# Battery_Management_and_Charging.net
KiCad netlist of a schematic drawn in Altium Designer
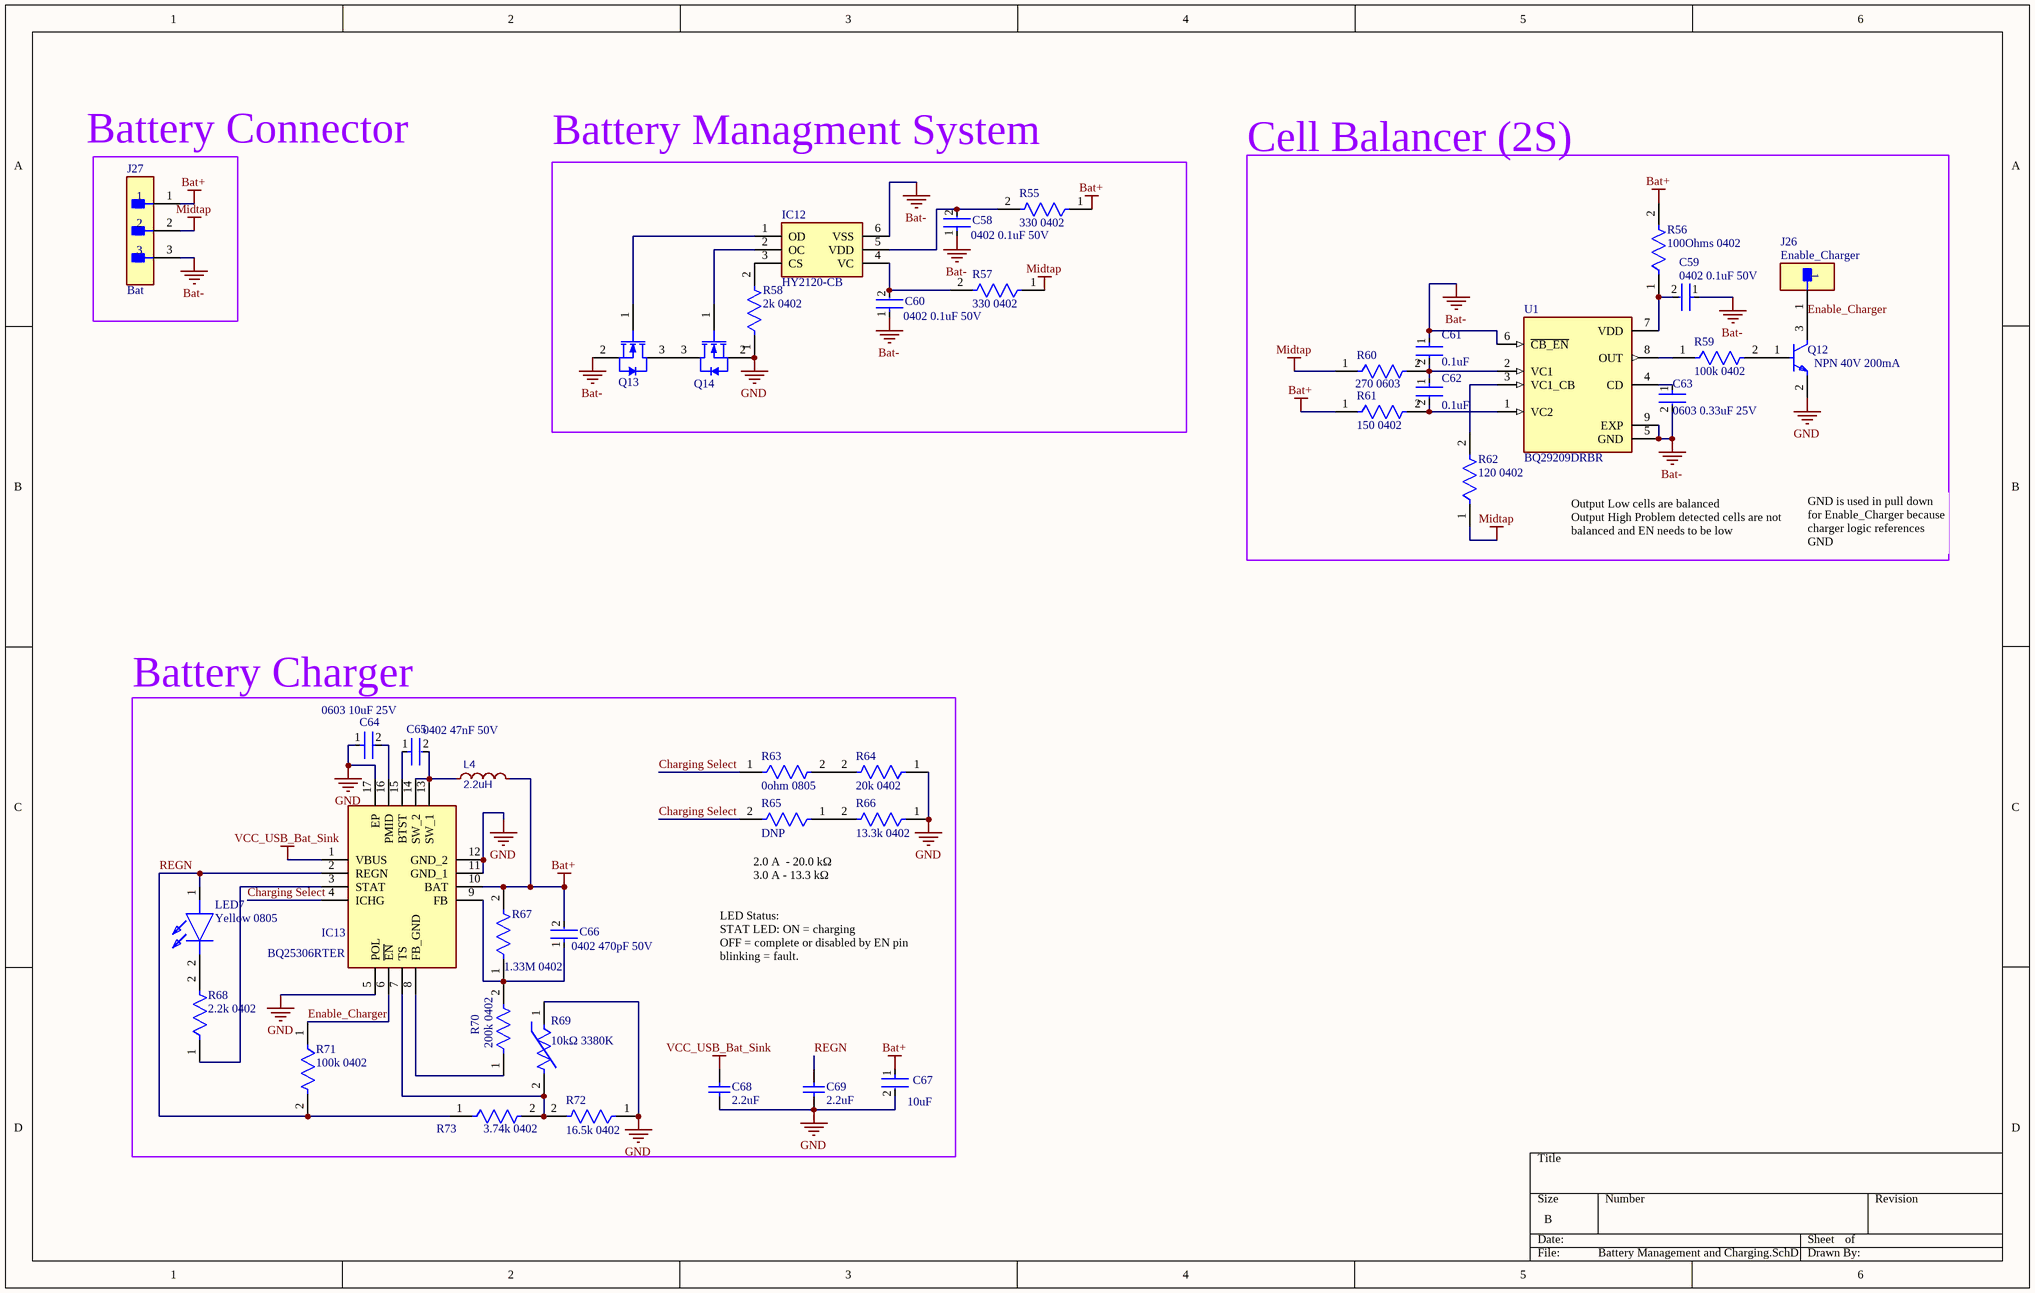
[diagram p0: Battery Management and Charging.SchDoc]

(export (version "E")
  (design (tool "Eeschema 10.0.6"))
  (components
    (comp (ref "C58")
      (value "0402 0.1uF 50V")
      (footprint "FP-C0402-BB-MFG")
      (description "C307331")
      (fields
        (field (name "TOLERANCE") "0.2")
        (field (name "OCTOPART") "https://octopart.com/c0402c104m3pac7867-kemet-84304880")
      )
      (libsource (lib "Altium Content Vault") (part "b4654b650e69147ec39a6b967a45e02"))
    )
    (comp (ref "C59")
      (value "0402 0.1uF 50V")
      (footprint "FP-C0402-BB-MFG")
      (description "C307331")
      (fields
        (field (name "TOLERANCE") "0.2")
        (field (name "OCTOPART") "https://octopart.com/c0402c104m3pac7867-kemet-84304880")
      )
      (libsource (lib "Altium Content Vault") (part "b4654b650e69147ec39a6b967a45e02"))
    )
    (comp (ref "C60")
      (value "0402 0.1uF 50V")
      (footprint "FP-C0402-BB-MFG")
      (description "C307331")
      (fields
        (field (name "TOLERANCE") "0.2")
        (field (name "OCTOPART") "https://octopart.com/c0402c104m3pac7867-kemet-84304880")
      )
      (libsource (lib "Altium Content Vault") (part "b4654b650e69147ec39a6b967a45e02"))
    )
    (comp (ref "C61")
      (value "0.1uF")
      (footprint "FP-C0402-BB-MFG")
      (description "C307331")
      (fields
        (field (name "TOLERANCE") "0.2")
        (field (name "OCTOPART") "https://octopart.com/c0402c104m3pac7867-kemet-84304880")
      )
      (libsource (lib "Altium Content Vault") (part "b4654b650e69147ec39a6b967a45e02"))
    )
    (comp (ref "C62")
      (value "0.1uF")
      (footprint "FP-C0402-BB-MFG")
      (description "C307331")
      (fields
        (field (name "TOLERANCE") "0.2")
        (field (name "OCTOPART") "https://octopart.com/c0402c104m3pac7867-kemet-84304880")
      )
      (libsource (lib "Altium Content Vault") (part "b4654b650e69147ec39a6b967a45e02"))
    )
    (comp (ref "C63")
      (value "0603 0.33uF 25V")
      (footprint "FP-CC0603-DC-MFG")
      (description "C1615")
      (fields (field (name "TOLERANCE") "10%"))
      (libsource (lib "Altium Content Vault") (part "b4654b650e69147ec39a6b967a45e02"))
    )
    (comp (ref "C64")
      (value "0603 10uF 25V")
      (footprint "FP-CC0603-DC-MFG")
      (description "C96446")
      (fields (field (name "TOLERANCE") "10%"))
      (libsource (lib "Altium Content Vault") (part "b4654b650e69147ec39a6b967a45e02"))
    )
    (comp (ref "C65")
      (value "0402 47nF 50V")
      (footprint "FP-C0402-BB-MFG")
      (description "C7393874")
      (fields
        (field (name "TOLERANCE") "0.2")
        (field (name "OCTOPART") "https://octopart.com/c0402c104m3pac7867-kemet-84304880")
      )
      (libsource (lib "Altium Content Vault") (part "b4654b650e69147ec39a6b967a45e02"))
    )
    (comp (ref "C66")
      (value "0402 470pF 50V")
      (footprint "FP-C0402-BB-MFG")
      (description "C1537")
      (fields
        (field (name "TOLERANCE") "0.2")
        (field (name "OCTOPART") "https://octopart.com/c0402c104m3pac7867-kemet-84304880")
      )
      (libsource (lib "Altium Content Vault") (part "b4654b650e69147ec39a6b967a45e02"))
    )
    (comp (ref "C67")
      (value "10uF")
      (footprint "FP-CC0603-DC-MFG")
      (description "C96446")
      (fields (field (name "TOLERANCE") "10%"))
      (libsource (lib "Altium Content Vault") (part "b4654b650e69147ec39a6b967a45e02"))
    )
    (comp (ref "C68")
      (value "2.2uF")
      (footprint "CAPC2013X94X50LL20T25")
      (description "C377773")
      (fields
        (field (name "PART NUMBER") "08051C102KAT4A")
        (field (name "MANUFACTURER") "AVX Interconnect / Elco")
      )
      (libsource (lib "Altium Content Vault") (part "CAP"))
    )
    (comp (ref "C69")
      (value "2.2uF")
      (footprint "CAPC2013X94X50LL20T25")
      (description "C377773")
      (fields
        (field (name "PART NUMBER") "08051C102KAT4A")
        (field (name "MANUFACTURER") "AVX Interconnect / Elco")
      )
      (libsource (lib "Altium Content Vault") (part "CAP"))
    )
    (comp (ref "IC12")
      (value "HY2120-CB")
      (footprint "PcbLib1:SOT95P280X140-6N")
      (description "C116509")
      (libsource (lib "*") (part "HY2120-CB"))
    )
    (comp (ref "IC13")
      (value "BQ25306RTER")
      (footprint "PcbLib1:QFN50P300X300X80-17N-D")
      (description "C3682611")
      (fields (field (name "MOUSER PART NUMBER") "595-BQ25306RTER"))
      (libsource (lib "*") (part "BQ25306RTER"))
    )
    (comp (ref "J26")
      (value "Enable_Charger")
      (footprint "FP-5015-MFG")
      (description "PC TEST POINT MINIATURE")
      (fields (field (name "MANUFACTURER PART NUMBER") "5015") (field (name "MANUFACTURER") "keystone"))
      (libsource (lib "Altium Content Vault") (part "dd45045ce8184df9e99e12baf3f412c"))
    )
    (comp (ref "J27")
      (value "Bat")
      (footprint "FP-TSW-103-14-G-S-MFG")
      (description "CONN HEADER VERT 3POS 2.54MM")
      (libsource (lib "Altium Content Vault") (part "cd3439d6ef35ae5d9b27ec4fdd3e828"))
    )
    (comp (ref "L4")
      (value "2.2uH")
      (footprint "2.2uH")
      (description "C177247")
      (fields
        (field (name "MANUFACTURER") "cjiang(长江微电)")
        (field (name "MANUFACTURER PART") "FXL0530-2R2-M")
        (field (name "CONTRIBUTOR") "LCSC")
      )
      (libsource (lib "Schlib1") (part "2.2uH"))
    )
    (comp (ref "LED7")
      (value "Yellow 0805")
      (footprint "SamacSys:KT0805G")
      (description "C2296")
      (fields (field (name "MANUFACTURER_PART_NUMBER") "KT-0805G"))
      (libsource (lib "*") (part "KT-0805G"))
    )
    (comp (ref "Q12")
      (value "NPN 40V 200mA")
      (footprint "FP-SOT23-IPC_A")
      (description "C364310")
      (libsource (lib "Altium Content Vault") (part "b44e953556f554d0102664c7d152cb4"))
    )
    (comp (ref "Q13")
      (value "Discharge Protection")
      (footprint "ONSC-SOT-23-3-318-08_V")
      (description "C20917")
      (fields (field (name "MANUFACTURER") "On Semiconductor") (field (name "PARTNUMBER") "2N7002LT1G"))
      (libsource (lib "Altium Content Vault") (part "ONSC-NMOS-G1S2D3-3"))
    )
    (comp (ref "Q14")
      (value "Discharge Protection")
      (footprint "ONSC-SOT-23-3-318-08_V")
      (description "C20917")
      (fields (field (name "MANUFACTURER") "On Semiconductor") (field (name "PARTNUMBER") "2N7002LT1G"))
      (libsource (lib "Altium Content Vault") (part "ONSC-NMOS-G1S2D3-3"))
    )
    (comp (ref "R55")
      (value "330 0402")
      (footprint "FP-RMCF0402-MFG")
      (description "C25104")
      (fields (field (name "TOLERANCE") "5%"))
      (libsource (lib "Altium Content Vault") (part "1029c3af85768c4190bb7ad29bc67b5"))
    )
    (comp (ref "R56")
      (value "100Ohms 0402")
      (footprint "FP-RMCF0402-MFG")
      (description "C25076")
      (fields (field (name "TOLERANCE") "5%"))
      (libsource (lib "Altium Content Vault") (part "1029c3af85768c4190bb7ad29bc67b5"))
    )
    (comp (ref "R57")
      (value "330 0402")
      (footprint "FP-RMCF0402-MFG")
      (description "C25104")
      (fields (field (name "TOLERANCE") "5%"))
      (libsource (lib "Altium Content Vault") (part "1029c3af85768c4190bb7ad29bc67b5"))
    )
    (comp (ref "R58")
      (value "2k 0402")
      (footprint "FP-RMCF0402-MFG")
      (description "C4109")
      (fields (field (name "TOLERANCE") "5%"))
      (libsource (lib "Altium Content Vault") (part "1029c3af85768c4190bb7ad29bc67b5"))
    )
    (comp (ref "R59")
      (value "100k 0402")
      (footprint "FP-RMCF0402-MFG")
      (description "C25741")
      (fields (field (name "TOLERANCE") "5%"))
      (libsource (lib "Altium Content Vault") (part "1029c3af85768c4190bb7ad29bc67b5"))
    )
    (comp (ref "R60")
      (value "270 0603")
      (footprint "FP-AC0603-MFG")
      (description "C22966")
      (fields (field (name "TOLERANCE") "1%"))
      (libsource (lib "Altium Content Vault") (part "1029c3af85768c4190bb7ad29bc67b5"))
    )
    (comp (ref "R61")
      (value "150 0402")
      (footprint "FP-RMCF0402-MFG")
      (description "C25082")
      (fields (field (name "TOLERANCE") "5%"))
      (libsource (lib "Altium Content Vault") (part "1029c3af85768c4190bb7ad29bc67b5"))
    )
    (comp (ref "R62")
      (value "120 0402")
      (footprint "FP-RMCF0402-MFG")
      (description "C25079")
      (fields (field (name "TOLERANCE") "5%"))
      (libsource (lib "Altium Content Vault") (part "1029c3af85768c4190bb7ad29bc67b5"))
    )
    (comp (ref "R63")
      (value "0ohm 0805")
      (footprint "FP-RN73R2A-IPC_C")
      (description "C17477")
      (libsource (lib "Altium Content Vault") (part "1029c3af85768c4190bb7ad29bc67b5"))
    )
    (comp (ref "R64")
      (value "20k 0402")
      (footprint "FP-RMCF0402-MFG")
      (description "C25765")
      (fields (field (name "TOLERANCE") "5%"))
      (libsource (lib "Altium Content Vault") (part "1029c3af85768c4190bb7ad29bc67b5"))
    )
    (comp (ref "R65")
      (value "DNP")
      (footprint "FP-RN73R2A-IPC_C")
      (description "DNP 0805")
      (libsource (lib "Altium Content Vault") (part "1029c3af85768c4190bb7ad29bc67b5"))
    )
    (comp (ref "R66")
      (value "13.3k 0402")
      (footprint "FP-RMCF0402-MFG")
      (description "C2974007")
      (fields (field (name "TOLERANCE") "5%"))
      (libsource (lib "Altium Content Vault") (part "1029c3af85768c4190bb7ad29bc67b5"))
    )
    (comp (ref "R67")
      (value "1.33M 0402")
      (footprint "FP-RMCF0402-MFG")
      (description "C5713265")
      (fields (field (name "TOLERANCE") "5%"))
      (libsource (lib "Altium Content Vault") (part "1029c3af85768c4190bb7ad29bc67b5"))
    )
    (comp (ref "R68")
      (value "2.2k 0402")
      (footprint "FP-AF0402-IPC_B")
      (description "C25879")
      (fields (field (name "TOLERANCE") "5%"))
      (libsource (lib "Altium Content Vault") (part "1029c3af85768c4190bb7ad29bc67b5"))
    )
    (comp (ref "R69")
      (value "10kΩ 3380K")
      (footprint "FP-NCP15-NCU15-0_05-IPC_A")
      (description "C178739")
      (libsource (lib "Altium Content Vault") (part "3b148a6ebabc5fb4d708a66c052d352"))
    )
    (comp (ref "R70")
      (value "200k 0402")
      (footprint "FP-RMCF0402-MFG")
      (description "C25764")
      (fields (field (name "TOLERANCE") "5%"))
      (libsource (lib "Altium Content Vault") (part "1029c3af85768c4190bb7ad29bc67b5"))
    )
    (comp (ref "R71")
      (value "100k 0402")
      (footprint "FP-RMCF0402-MFG")
      (description "C25741")
      (fields (field (name "TOLERANCE") "5%"))
      (libsource (lib "Altium Content Vault") (part "1029c3af85768c4190bb7ad29bc67b5"))
    )
    (comp (ref "R72")
      (value "16.5k 0402")
      (footprint "FP-RMCF0402-MFG")
      (description "C226807")
      (fields (field (name "TOLERANCE") "5%"))
      (libsource (lib "Altium Content Vault") (part "1029c3af85768c4190bb7ad29bc67b5"))
    )
    (comp (ref "R73")
      (value "3.74k 0402")
      (footprint "FP-RMCF0402-MFG")
      (description "C2986585")
      (fields (field (name "TOLERANCE") "5%"))
      (libsource (lib "Altium Content Vault") (part "1029c3af85768c4190bb7ad29bc67b5"))
    )
    (comp (ref "U1")
      (value "BQ29209DRBR")
      (footprint "Cell Balancer")
      (description "C139352")
      (fields (field (name "MF") "Texas Instruments"))
      (libsource (lib "Schlib1") (part "BQ29209DRBR"))
    )
  )
  (nets
    (net (code "1") (name "/Charging Select") (class "Default")
      (node (ref "IC13") (pin "4") (pinfunction "ICHG_4") (pintype "passive"))
      (node (ref "R63") (pin "1") (pinfunction "1_1") (pintype "passive"))
      (node (ref "R65") (pin "2") (pinfunction "2_2") (pintype "passive"))
    )
    (net (code "2") (name "/Enable_Charger") (class "Default")
      (node (ref "IC13") (pin "6") (pinfunction "~{EN}_6") (pintype "passive"))
      (node (ref "J26") (pin "1") (pinfunction "1_1") (pintype "passive"))
      (node (ref "Q12") (pin "3") (pinfunction "C_3") (pintype "passive"))
      (node (ref "R71") (pin "1") (pinfunction "1_1") (pintype "passive"))
    )
    (net (code "3") (name "/REGN") (class "Default")
      (node (ref "C69") (pin "2") (pinfunction "2_2") (pintype "passive"))
      (node (ref "IC13") (pin "2") (pinfunction "REGN_2") (pintype "passive"))
      (node (ref "LED7") (pin "1") (pinfunction "A_1") (pintype "passive"))
      (node (ref "R71") (pin "2") (pinfunction "2_2") (pintype "passive"))
      (node (ref "R73") (pin "1") (pinfunction "1_1") (pintype "passive"))
    )
    (net (code "4") (name "Bat+") (class "Default")
      (node (ref "C66") (pin "2") (pinfunction "2_2") (pintype "passive"))
      (node (ref "C67") (pin "1") (pinfunction "1_1") (pintype "passive"))
      (node (ref "IC13") (pin "10") (pinfunction "BAT_10") (pintype "passive"))
      (node (ref "J27") (pin "1") (pinfunction "1_1") (pintype "passive"))
      (node (ref "L4") (pin "2") (pinfunction "2_2") (pintype "passive"))
      (node (ref "R55") (pin "1") (pinfunction "1_1") (pintype "passive"))
      (node (ref "R56") (pin "2") (pinfunction "2_2") (pintype "passive"))
      (node (ref "R61") (pin "1") (pinfunction "1_1") (pintype "passive"))
      (node (ref "R67") (pin "2") (pinfunction "2_2") (pintype "passive"))
    )
    (net (code "5") (name "Bat-") (class "Default")
      (node (ref "C58") (pin "1") (pinfunction "1_1") (pintype "passive"))
      (node (ref "C59") (pin "1") (pinfunction "1_1") (pintype "passive"))
      (node (ref "C60") (pin "1") (pinfunction "1_1") (pintype "passive"))
      (node (ref "C61") (pin "1") (pinfunction "1_1") (pintype "passive"))
      (node (ref "C63") (pin "2") (pinfunction "2_2") (pintype "passive"))
      (node (ref "IC12") (pin "6") (pinfunction "VSS_6") (pintype "passive"))
      (node (ref "J27") (pin "3") (pinfunction "3_3") (pintype "passive"))
      (node (ref "Q13") (pin "2") (pinfunction "S_2") (pintype "passive"))
      (node (ref "U1") (pin "5") (pinfunction "GND_5") (pintype "power_in"))
      (node (ref "U1") (pin "6") (pinfunction "~{CB_EN}_6") (pintype "input"))
      (node (ref "U1") (pin "9") (pinfunction "EXP_9") (pintype "power_in"))
    )
    (net (code "6") (name "GND") (class "Default")
      (node (ref "C64") (pin "1") (pinfunction "1_1") (pintype "passive"))
      (node (ref "C67") (pin "2") (pinfunction "2_2") (pintype "passive"))
      (node (ref "C68") (pin "1") (pinfunction "1_1") (pintype "passive"))
      (node (ref "C69") (pin "1") (pinfunction "1_1") (pintype "passive"))
      (node (ref "IC13") (pin "11") (pinfunction "GND_1_11") (pintype "passive"))
      (node (ref "IC13") (pin "12") (pinfunction "GND_2_12") (pintype "passive"))
      (node (ref "IC13") (pin "17") (pinfunction "EP_17") (pintype "passive"))
      (node (ref "IC13") (pin "5") (pinfunction "POL_5") (pintype "passive"))
      (node (ref "Q12") (pin "2") (pinfunction "E_2") (pintype "passive"))
      (node (ref "Q14") (pin "2") (pinfunction "S_2") (pintype "passive"))
      (node (ref "R58") (pin "1") (pinfunction "1_1") (pintype "passive"))
      (node (ref "R64") (pin "1") (pinfunction "1_1") (pintype "passive"))
      (node (ref "R66") (pin "1") (pinfunction "1_1") (pintype "passive"))
      (node (ref "R69") (pin "1") (pinfunction "1_1") (pintype "passive"))
      (node (ref "R72") (pin "1") (pinfunction "1_1") (pintype "passive"))
    )
    (net (code "7") (name "Midtap") (class "Default")
      (node (ref "J27") (pin "2") (pinfunction "2_2") (pintype "passive"))
      (node (ref "R57") (pin "1") (pinfunction "1_1") (pintype "passive"))
      (node (ref "R60") (pin "1") (pinfunction "1_1") (pintype "passive"))
      (node (ref "R62") (pin "1") (pinfunction "1_1") (pintype "passive"))
    )
    (net (code "8") (name "Net-(IC12-CS)") (class "Default")
      (node (ref "IC12") (pin "3") (pinfunction "CS_3") (pintype "passive"))
      (node (ref "R58") (pin "2") (pinfunction "2_2") (pintype "passive"))
    )
    (net (code "9") (name "Net-(IC12-OC)") (class "Default")
      (node (ref "IC12") (pin "2") (pinfunction "OC_2") (pintype "passive"))
      (node (ref "Q14") (pin "1") (pinfunction "G_1") (pintype "passive"))
    )
    (net (code "10") (name "Net-(IC12-OD)") (class "Default")
      (node (ref "IC12") (pin "1") (pinfunction "OD_1") (pintype "passive"))
      (node (ref "Q13") (pin "1") (pinfunction "G_1") (pintype "passive"))
    )
    (net (code "11") (name "Net-(IC12-VC)") (class "Default")
      (node (ref "C60") (pin "2") (pinfunction "2_2") (pintype "passive"))
      (node (ref "IC12") (pin "4") (pinfunction "VC_4") (pintype "passive"))
      (node (ref "R57") (pin "2") (pinfunction "2_2") (pintype "passive"))
    )
    (net (code "12") (name "Net-(IC12-VDD)") (class "Default")
      (node (ref "C58") (pin "2") (pinfunction "2_2") (pintype "passive"))
      (node (ref "IC12") (pin "5") (pinfunction "VDD_5") (pintype "passive"))
      (node (ref "R55") (pin "2") (pinfunction "2_2") (pintype "passive"))
    )
    (net (code "13") (name "Net-(IC13-BTST)") (class "Default")
      (node (ref "C65") (pin "1") (pinfunction "1_1") (pintype "passive"))
      (node (ref "IC13") (pin "15") (pinfunction "BTST_15") (pintype "passive"))
    )
    (net (code "14") (name "Net-(IC13-FB)") (class "Default")
      (node (ref "C66") (pin "1") (pinfunction "1_1") (pintype "passive"))
      (node (ref "IC13") (pin "9") (pinfunction "FB_9") (pintype "passive"))
      (node (ref "R67") (pin "1") (pinfunction "1_1") (pintype "passive"))
      (node (ref "R70") (pin "2") (pinfunction "2_2") (pintype "passive"))
    )
    (net (code "15") (name "Net-(IC13-FB_GND)") (class "Default")
      (node (ref "IC13") (pin "8") (pinfunction "FB_GND_8") (pintype "passive"))
      (node (ref "R70") (pin "1") (pinfunction "1_1") (pintype "passive"))
    )
    (net (code "16") (name "Net-(IC13-PMID)") (class "Default")
      (node (ref "C64") (pin "2") (pinfunction "2_2") (pintype "passive"))
      (node (ref "IC13") (pin "16") (pinfunction "PMID_16") (pintype "passive"))
    )
    (net (code "17") (name "Net-(IC13-STAT)") (class "Default")
      (node (ref "IC13") (pin "3") (pinfunction "STAT_3") (pintype "passive"))
      (node (ref "R68") (pin "1") (pinfunction "1_1") (pintype "passive"))
    )
    (net (code "18") (name "Net-(IC13-SW_1)") (class "Default")
      (node (ref "C65") (pin "2") (pinfunction "2_2") (pintype "passive"))
      (node (ref "IC13") (pin "13") (pinfunction "SW_1_13") (pintype "passive"))
      (node (ref "IC13") (pin "14") (pinfunction "SW_2_14") (pintype "passive"))
      (node (ref "L4") (pin "1") (pinfunction "1_1") (pintype "passive"))
    )
    (net (code "19") (name "Net-(IC13-TS)") (class "Default")
      (node (ref "IC13") (pin "7") (pinfunction "TS_7") (pintype "passive"))
      (node (ref "R69") (pin "2") (pinfunction "2_2") (pintype "passive"))
      (node (ref "R72") (pin "2") (pinfunction "2_2") (pintype "passive"))
      (node (ref "R73") (pin "2") (pinfunction "2_2") (pintype "passive"))
    )
    (net (code "20") (name "Net-(LED7-K)") (class "Default")
      (node (ref "LED7") (pin "2") (pinfunction "K_2") (pintype "passive"))
      (node (ref "R68") (pin "2") (pinfunction "2_2") (pintype "passive"))
    )
    (net (code "21") (name "Net-(Q12-B)") (class "Default")
      (node (ref "Q12") (pin "1") (pinfunction "B_1") (pintype "passive"))
      (node (ref "R59") (pin "2") (pinfunction "2_2") (pintype "passive"))
    )
    (net (code "22") (name "Net-(Q13-D)") (class "Default")
      (node (ref "Q13") (pin "3") (pinfunction "D_3") (pintype "passive"))
      (node (ref "Q14") (pin "3") (pinfunction "D_3") (pintype "passive"))
    )
    (net (code "23") (name "Net-(R63-Pad2)") (class "Default")
      (node (ref "R63") (pin "2") (pinfunction "2_2") (pintype "passive"))
      (node (ref "R64") (pin "2") (pinfunction "2_2") (pintype "passive"))
    )
    (net (code "24") (name "Net-(R65-Pad1)") (class "Default")
      (node (ref "R65") (pin "1") (pinfunction "1_1") (pintype "passive"))
      (node (ref "R66") (pin "2") (pinfunction "2_2") (pintype "passive"))
    )
    (net (code "25") (name "Net-(U1-CD)") (class "Default")
      (node (ref "C63") (pin "1") (pinfunction "1_1") (pintype "passive"))
      (node (ref "U1") (pin "4") (pinfunction "CD_4") (pintype "passive"))
    )
    (net (code "26") (name "Net-(U1-OUT)") (class "Default")
      (node (ref "R59") (pin "1") (pinfunction "1_1") (pintype "passive"))
      (node (ref "U1") (pin "8") (pinfunction "OUT_8") (pintype "output"))
    )
    (net (code "27") (name "Net-(U1-VC1)") (class "Default")
      (node (ref "C61") (pin "2") (pinfunction "2_2") (pintype "passive"))
      (node (ref "C62") (pin "1") (pinfunction "1_1") (pintype "passive"))
      (node (ref "R60") (pin "2") (pinfunction "2_2") (pintype "passive"))
      (node (ref "U1") (pin "2") (pinfunction "VC1_2") (pintype "input"))
    )
    (net (code "28") (name "Net-(U1-VC1_CB)") (class "Default")
      (node (ref "R62") (pin "2") (pinfunction "2_2") (pintype "passive"))
      (node (ref "U1") (pin "3") (pinfunction "VC1_CB_3") (pintype "input"))
    )
    (net (code "29") (name "Net-(U1-VC2)") (class "Default")
      (node (ref "C62") (pin "2") (pinfunction "2_2") (pintype "passive"))
      (node (ref "R61") (pin "2") (pinfunction "2_2") (pintype "passive"))
      (node (ref "U1") (pin "1") (pinfunction "VC2_1") (pintype "input"))
    )
    (net (code "30") (name "Net-(U1-VDD)") (class "Default")
      (node (ref "C59") (pin "2") (pinfunction "2_2") (pintype "passive"))
      (node (ref "R56") (pin "1") (pinfunction "1_1") (pintype "passive"))
      (node (ref "U1") (pin "7") (pinfunction "VDD_7") (pintype "power_in"))
    )
    (net (code "31") (name "VCC_USB_Bat_Sink") (class "Default")
      (node (ref "C68") (pin "2") (pinfunction "2_2") (pintype "passive"))
      (node (ref "IC13") (pin "1") (pinfunction "VBUS_1") (pintype "passive"))
    )
  )
)
